# Res_Cut.net
KiCad netlist of a schematic drawn in EAGLE
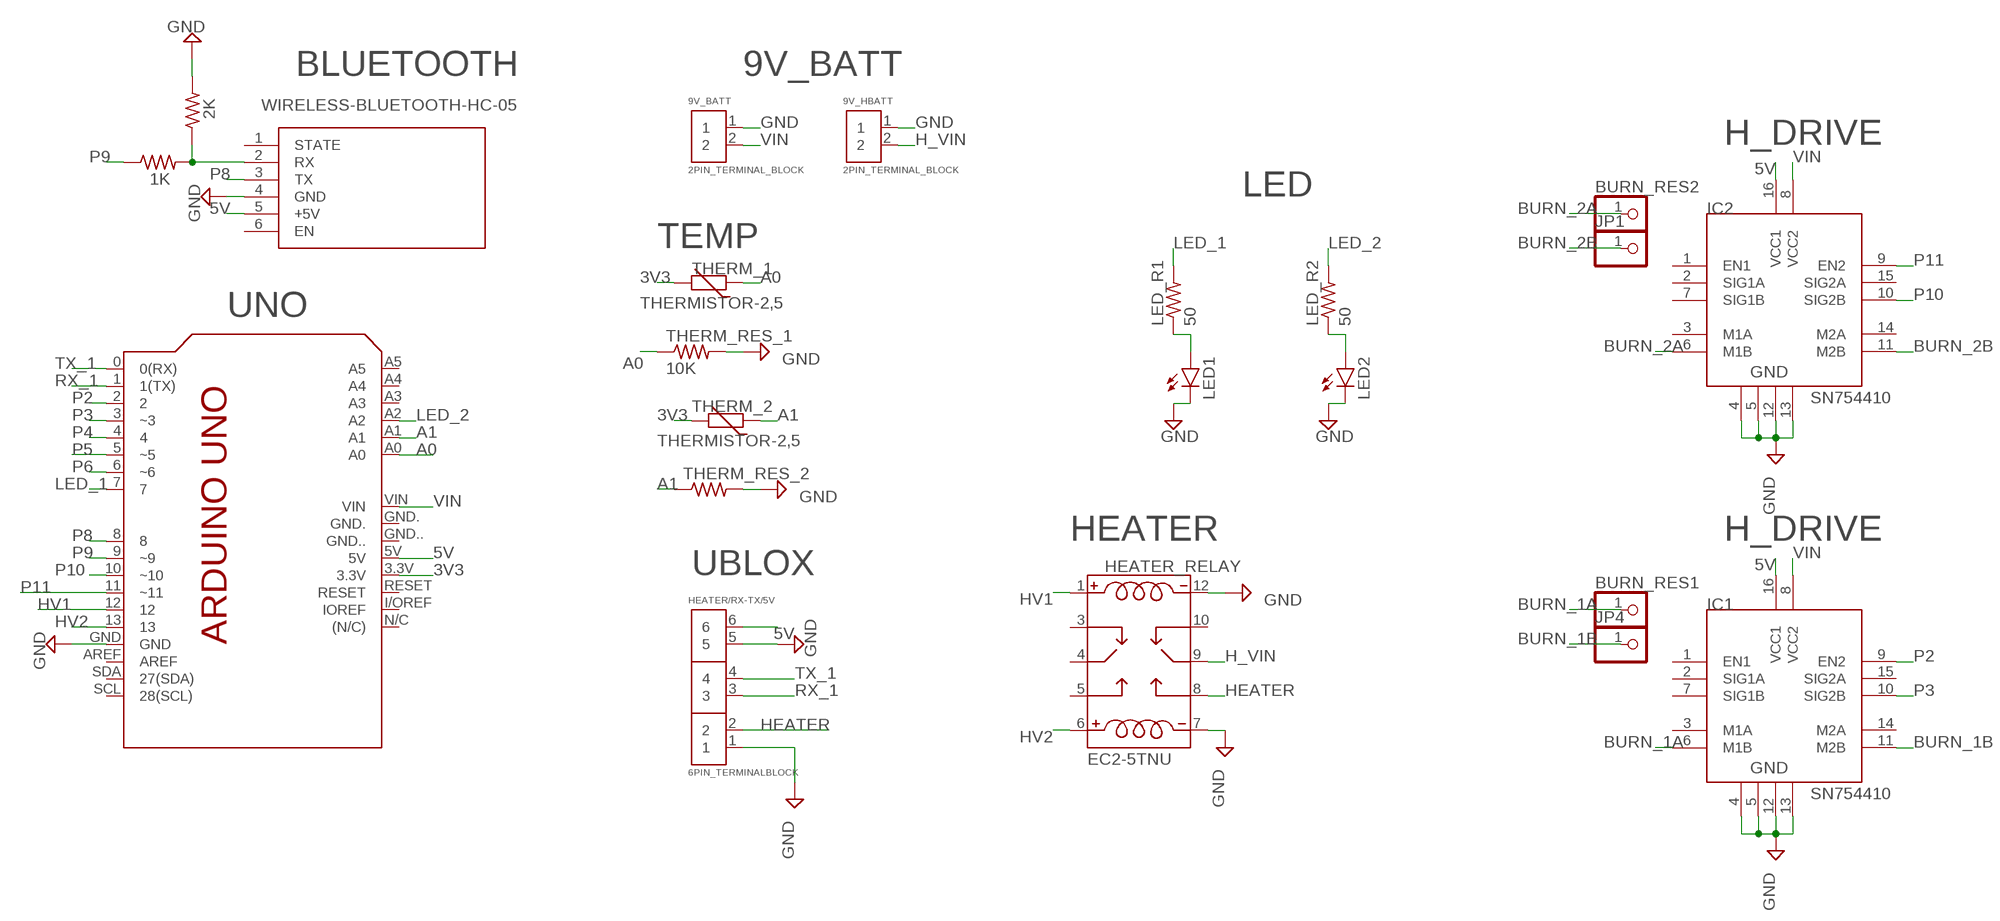
[diagram p0: schematic, sheet 1]

(export (version "E")
  (design (tool "Eeschema 10.0.6"))
  (components
    (comp (ref "9V_BATT")
      (value "2PIN_TERMINAL_BLOCK")
      (footprint "eagle-import:2PIN_TERMINAL_BLOCK")
      (fields
        (field (name "COMMENT") "282834-2")
        (field (name "DIGI-KEY_PART_NUMBER") "A98333-ND")
        (field (name "MF") "TE Connectivity")
      )
      (libsource (lib "eagle-import") (part "2PIN_TERMINAL_BLOCK"))
    )
    (comp (ref "9V_HBATT")
      (value "2PIN_TERMINAL_BLOCK")
      (footprint "eagle-import:2PIN_TERMINAL_BLOCK")
      (fields
        (field (name "COMMENT") "282834-2")
        (field (name "DIGI-KEY_PART_NUMBER") "A98333-ND")
        (field (name "MF") "TE Connectivity")
      )
      (libsource (lib "eagle-import") (part "2PIN_TERMINAL_BLOCK"))
    )
    (comp (ref "BLUE_R1")
      (value "1K")
      (footprint "eagle-import:0204_7")
      (libsource (lib "eagle-import") (part "R-US_0204/7"))
    )
    (comp (ref "BLUE_R2")
      (value "2K")
      (footprint "eagle-import:0204_7")
      (libsource (lib "eagle-import") (part "R-US_0204/7"))
    )
    (comp (ref "BURN_RES1")
      (value "PINHD-1X1CB")
      (footprint "eagle-import:1X01-CLEANBIG")
      (libsource (lib "eagle-import") (part "PINHD-1X1CB"))
    )
    (comp (ref "BURN_RES2")
      (value "PINHD-1X1CB")
      (footprint "eagle-import:1X01-CLEANBIG")
      (libsource (lib "eagle-import") (part "PINHD-1X1CB"))
    )
    (comp (ref "HEATER/RX-TX/5V")
      (value "6PIN_TERMINALBLOCK")
      (footprint "eagle-import:6PIN_TERMINALBLOCK")
      (libsource (lib "eagle-import") (part "6PIN_TERMINALBLOCK"))
    )
    (comp (ref "HEATER_RELAY")
      (value "EC2-5TNU")
      (footprint "eagle-import:RELAY_EC2-5TNU")
      (fields (field (name "MF") "KEMET"))
      (libsource (lib "eagle-import") (part "EC2-5TNU"))
    )
    (comp (ref "IC1")
      (value "SN754410")
      (footprint "eagle-import:DIP16")
      (libsource (lib "eagle-import") (part "SN754410"))
    )
    (comp (ref "IC2")
      (value "SN754410")
      (footprint "eagle-import:DIP16")
      (libsource (lib "eagle-import") (part "SN754410"))
    )
    (comp (ref "JP1")
      (value "PINHD-1X1CB")
      (footprint "eagle-import:1X01-CLEANBIG")
      (libsource (lib "eagle-import") (part "PINHD-1X1CB"))
    )
    (comp (ref "JP4")
      (value "PINHD-1X1CB")
      (footprint "eagle-import:1X01-CLEANBIG")
      (libsource (lib "eagle-import") (part "PINHD-1X1CB"))
    )
    (comp (ref "LED1")
      (value "TLLR4400")
      (footprint "eagle-import:LED3MM")
      (fields (field (name "MF") "VISHAY SEMICONDUCTOR"))
      (libsource (lib "eagle-import") (part "TLLR4400"))
    )
    (comp (ref "LED2")
      (value "TLLR4400")
      (footprint "eagle-import:LED3MM")
      (fields (field (name "MF") "VISHAY SEMICONDUCTOR"))
      (libsource (lib "eagle-import") (part "TLLR4400"))
    )
    (comp (ref "LED_R1")
      (value "50")
      (footprint "eagle-import:0204_7")
      (libsource (lib "eagle-import") (part "resistor_348_R-US_0204/7"))
    )
    (comp (ref "LED_R2")
      (value "50")
      (footprint "eagle-import:0204_7")
      (libsource (lib "eagle-import") (part "resistor_348_R-US_0204/7"))
    )
    (comp (ref "PCB1")
      (value "ARDUINO_UNO")
      (footprint "eagle-import:ARDUINO_UNO")
      (libsource (lib "eagle-import") (part "ARDUINO_UNO"))
    )
    (comp (ref "THERM_1")
      (value "THERMISTOR-2,5")
      (footprint "eagle-import:RS-2,5")
      (libsource (lib "eagle-import") (part "THERMISTOR-2,5"))
    )
    (comp (ref "THERM_2")
      (value "THERMISTOR-2,5")
      (footprint "eagle-import:RS-2,5")
      (libsource (lib "eagle-import") (part "THERMISTOR-2,5"))
    )
    (comp (ref "THERM_RES_1")
      (value "10K")
      (footprint "eagle-import:0204_7")
      (libsource (lib "eagle-import") (part "R-US_0204/7"))
    )
    (comp (ref "THERM_RES_2")
      (value "10K")
      (footprint "eagle-import:0204_7")
      (libsource (lib "eagle-import") (part "R-US_0204/7"))
    )
    (comp (ref "U$1")
      (value "WIRELESS-BLUETOOTH-HC-05")
      (footprint "eagle-import:WIRELESS-BLUETOOTH-HC-05")
      (libsource (lib "eagle-import") (part "WIRELESS-BLUETOOTH-HC-05"))
    )
  )
  (nets
    (net (code "1") (name "/3V3") (class "Default")
      (node (ref "PCB1") (pin "3.3V") (pinfunction "3.3V_3.3V") (pintype "bidirectional"))
      (node (ref "THERM_1") (pin "2") (pinfunction "2_2") (pintype "passive"))
      (node (ref "THERM_2") (pin "2") (pinfunction "2_2") (pintype "passive"))
    )
    (net (code "2") (name "/5V") (class "Default")
      (node (ref "HEATER/RX-TX/5V") (pin "6") (pinfunction "6_6") (pintype "passive"))
      (node (ref "IC1") (pin "16") (pinfunction "VCC1_16") (pintype "power_in"))
      (node (ref "IC2") (pin "16") (pinfunction "VCC1_16") (pintype "power_in"))
      (node (ref "PCB1") (pin "5V") (pinfunction "5V_5V") (pintype "bidirectional"))
      (node (ref "U$1") (pin "5") (pinfunction "+5V_5") (pintype "power_in"))
    )
    (net (code "3") (name "/A0") (class "Default")
      (node (ref "PCB1") (pin "A0") (pinfunction "A0_A0") (pintype "bidirectional"))
      (node (ref "THERM_1") (pin "1") (pinfunction "1_1") (pintype "passive"))
      (node (ref "THERM_RES_1") (pin "1") (pinfunction "1_1") (pintype "passive"))
    )
    (net (code "4") (name "/A1") (class "Default")
      (node (ref "PCB1") (pin "A1") (pinfunction "A1_A1") (pintype "bidirectional"))
      (node (ref "THERM_2") (pin "1") (pinfunction "1_1") (pintype "passive"))
      (node (ref "THERM_RES_2") (pin "1") (pinfunction "1_1") (pintype "passive"))
    )
    (net (code "5") (name "/BURN_1A") (class "Default")
      (node (ref "BURN_RES1") (pin "1") (pinfunction "1_1") (pintype "passive"))
      (node (ref "IC1") (pin "6") (pinfunction "M1B_6") (pintype "bidirectional"))
    )
    (net (code "6") (name "/BURN_1B") (class "Default")
      (node (ref "IC1") (pin "11") (pinfunction "M2B_11") (pintype "bidirectional"))
      (node (ref "JP4") (pin "1") (pinfunction "1_1") (pintype "passive"))
    )
    (net (code "7") (name "/BURN_2A") (class "Default")
      (node (ref "BURN_RES2") (pin "1") (pinfunction "1_1") (pintype "passive"))
      (node (ref "IC2") (pin "6") (pinfunction "M1B_6") (pintype "bidirectional"))
    )
    (net (code "8") (name "/BURN_2B") (class "Default")
      (node (ref "IC2") (pin "11") (pinfunction "M2B_11") (pintype "bidirectional"))
      (node (ref "JP1") (pin "1") (pinfunction "1_1") (pintype "passive"))
    )
    (net (code "9") (name "/HEATER") (class "Default")
      (node (ref "HEATER/RX-TX/5V") (pin "2") (pinfunction "2_2") (pintype "passive"))
      (node (ref "HEATER_RELAY") (pin "8") (pinfunction "NO_8") (pintype "passive"))
    )
    (net (code "10") (name "/HV1") (class "Default")
      (node (ref "HEATER_RELAY") (pin "1") (pinfunction "C1_1") (pintype "passive"))
      (node (ref "PCB1") (pin "12") (pinfunction "12_12") (pintype "bidirectional"))
    )
    (net (code "11") (name "/HV2") (class "Default")
      (node (ref "HEATER_RELAY") (pin "6") (pinfunction "C3_6") (pintype "passive"))
      (node (ref "PCB1") (pin "13") (pinfunction "13_13") (pintype "bidirectional"))
    )
    (net (code "12") (name "/H_VIN") (class "Default")
      (node (ref "9V_HBATT") (pin "2") (pinfunction "2_2") (pintype "passive"))
      (node (ref "HEATER_RELAY") (pin "9") (pinfunction "M_9") (pintype "passive"))
    )
    (net (code "13") (name "/LED_1") (class "Default")
      (node (ref "LED_R1") (pin "2") (pinfunction "2_2") (pintype "passive"))
      (node (ref "PCB1") (pin "7") (pinfunction "7_7") (pintype "bidirectional"))
    )
    (net (code "14") (name "/LED_2") (class "Default")
      (node (ref "LED_R2") (pin "2") (pinfunction "2_2") (pintype "passive"))
      (node (ref "PCB1") (pin "A2") (pinfunction "A2_A2") (pintype "bidirectional"))
    )
    (net (code "15") (name "/P2") (class "Default")
      (node (ref "IC1") (pin "9") (pinfunction "EN2_9") (pintype "bidirectional"))
      (node (ref "PCB1") (pin "2") (pinfunction "2_2") (pintype "bidirectional"))
    )
    (net (code "16") (name "/P3") (class "Default")
      (node (ref "IC1") (pin "10") (pinfunction "SIG2B_10") (pintype "bidirectional"))
      (node (ref "PCB1") (pin "3") (pinfunction "~{3}_3") (pintype "bidirectional"))
    )
    (net (code "17") (name "/P4") (class "Default")
      (node (ref "PCB1") (pin "4") (pinfunction "4_4") (pintype "bidirectional"))
    )
    (net (code "18") (name "/P5") (class "Default")
      (node (ref "PCB1") (pin "5") (pinfunction "~{5}_5") (pintype "bidirectional"))
    )
    (net (code "19") (name "/P6") (class "Default")
      (node (ref "PCB1") (pin "6") (pinfunction "~{6}_6") (pintype "bidirectional"))
    )
    (net (code "20") (name "/P8") (class "Default")
      (node (ref "PCB1") (pin "8") (pinfunction "8_8") (pintype "bidirectional"))
      (node (ref "U$1") (pin "3") (pinfunction "TX_3") (pintype "bidirectional"))
    )
    (net (code "21") (name "/P9") (class "Default")
      (node (ref "BLUE_R1") (pin "1") (pinfunction "1_1") (pintype "passive"))
      (node (ref "PCB1") (pin "9") (pinfunction "~{9}_9") (pintype "bidirectional"))
    )
    (net (code "22") (name "/P10") (class "Default")
      (node (ref "IC2") (pin "10") (pinfunction "SIG2B_10") (pintype "bidirectional"))
      (node (ref "PCB1") (pin "10") (pinfunction "~{10}_10") (pintype "bidirectional"))
    )
    (net (code "23") (name "/P11") (class "Default")
      (node (ref "IC2") (pin "9") (pinfunction "EN2_9") (pintype "bidirectional"))
      (node (ref "PCB1") (pin "11") (pinfunction "~{11}_11") (pintype "bidirectional"))
    )
    (net (code "24") (name "/RX_1") (class "Default")
      (node (ref "HEATER/RX-TX/5V") (pin "3") (pinfunction "3_3") (pintype "passive"))
      (node (ref "PCB1") (pin "1") (pinfunction "1(TX)_1") (pintype "bidirectional"))
    )
    (net (code "25") (name "/TX_1") (class "Default")
      (node (ref "HEATER/RX-TX/5V") (pin "4") (pinfunction "4_4") (pintype "passive"))
      (node (ref "PCB1") (pin "0") (pinfunction "0(RX)_0") (pintype "bidirectional"))
    )
    (net (code "26") (name "/VIN") (class "Default")
      (node (ref "9V_BATT") (pin "2") (pinfunction "2_2") (pintype "passive"))
      (node (ref "IC1") (pin "8") (pinfunction "VCC2_8") (pintype "power_in"))
      (node (ref "IC2") (pin "8") (pinfunction "VCC2_8") (pintype "power_in"))
      (node (ref "PCB1") (pin "VIN") (pinfunction "VIN_VIN") (pintype "bidirectional"))
    )
    (net (code "27") (name "GND") (class "Default")
      (node (ref "9V_BATT") (pin "1") (pinfunction "1_1") (pintype "passive"))
      (node (ref "9V_HBATT") (pin "1") (pinfunction "1_1") (pintype "passive"))
      (node (ref "BLUE_R2") (pin "2") (pinfunction "2_2") (pintype "passive"))
      (node (ref "HEATER/RX-TX/5V") (pin "1") (pinfunction "1_1") (pintype "passive"))
      (node (ref "HEATER/RX-TX/5V") (pin "5") (pinfunction "5_5") (pintype "passive"))
      (node (ref "HEATER_RELAY") (pin "12") (pinfunction "C2_12") (pintype "passive"))
      (node (ref "HEATER_RELAY") (pin "7") (pinfunction "C4_7") (pintype "passive"))
      (node (ref "IC1") (pin "12") (pinfunction "P12_12") (pintype "power_in"))
      (node (ref "IC1") (pin "13") (pinfunction "P13_13") (pintype "power_in"))
      (node (ref "IC1") (pin "4") (pinfunction "P4_4") (pintype "power_in"))
      (node (ref "IC1") (pin "5") (pinfunction "P5_5") (pintype "power_in"))
      (node (ref "IC2") (pin "12") (pinfunction "P12_12") (pintype "power_in"))
      (node (ref "IC2") (pin "13") (pinfunction "P13_13") (pintype "power_in"))
      (node (ref "IC2") (pin "4") (pinfunction "P4_4") (pintype "power_in"))
      (node (ref "IC2") (pin "5") (pinfunction "P5_5") (pintype "power_in"))
      (node (ref "LED1") (pin "K") (pinfunction "C_K") (pintype "passive"))
      (node (ref "LED2") (pin "K") (pinfunction "C_K") (pintype "passive"))
      (node (ref "PCB1") (pin "GND") (pinfunction "GND_GND") (pintype "bidirectional"))
      (node (ref "THERM_RES_1") (pin "2") (pinfunction "2_2") (pintype "passive"))
      (node (ref "THERM_RES_2") (pin "2") (pinfunction "2_2") (pintype "passive"))
      (node (ref "U$1") (pin "4") (pinfunction "GND_4") (pintype "power_in"))
    )
    (net (code "28") (name "Net-(LED1-PadA)") (class "Default")
      (node (ref "LED1") (pin "A") (pinfunction "A_A") (pintype "passive"))
      (node (ref "LED_R1") (pin "1") (pinfunction "1_1") (pintype "passive"))
    )
    (net (code "29") (name "Net-(LED2-PadA)") (class "Default")
      (node (ref "LED2") (pin "A") (pinfunction "A_A") (pintype "passive"))
      (node (ref "LED_R2") (pin "1") (pinfunction "1_1") (pintype "passive"))
    )
    (net (code "30") (name "Net-(U$1-RX)") (class "Default")
      (node (ref "BLUE_R1") (pin "2") (pinfunction "2_2") (pintype "passive"))
      (node (ref "BLUE_R2") (pin "1") (pinfunction "1_1") (pintype "passive"))
      (node (ref "U$1") (pin "2") (pinfunction "RX_2") (pintype "bidirectional"))
    )
    (net (code "31") (name "unconnected-(HEATER_RELAY-M1-Pad4)") (class "Default")
      (node (ref "HEATER_RELAY") (pin "4") (pinfunction "M1_4") (pintype "passive"))
    )
    (net (code "32") (name "unconnected-(HEATER_RELAY-NC-Pad10)") (class "Default")
      (node (ref "HEATER_RELAY") (pin "10") (pinfunction "NC_10") (pintype "passive"))
    )
    (net (code "33") (name "unconnected-(HEATER_RELAY-NC1-Pad3)") (class "Default")
      (node (ref "HEATER_RELAY") (pin "3") (pinfunction "NC1_3") (pintype "passive"))
    )
    (net (code "34") (name "unconnected-(HEATER_RELAY-NO1-Pad5)") (class "Default")
      (node (ref "HEATER_RELAY") (pin "5") (pinfunction "NO1_5") (pintype "passive"))
    )
    (net (code "35") (name "unconnected-(IC1-EN1-Pad1)") (class "Default")
      (node (ref "IC1") (pin "1") (pinfunction "EN1_1") (pintype "bidirectional"))
    )
    (net (code "36") (name "unconnected-(IC1-M1A-Pad3)") (class "Default")
      (node (ref "IC1") (pin "3") (pinfunction "M1A_3") (pintype "bidirectional"))
    )
    (net (code "37") (name "unconnected-(IC1-M2A-Pad14)") (class "Default")
      (node (ref "IC1") (pin "14") (pinfunction "M2A_14") (pintype "bidirectional"))
    )
    (net (code "38") (name "unconnected-(IC1-SIG1A-Pad2)") (class "Default")
      (node (ref "IC1") (pin "2") (pinfunction "SIG1A_2") (pintype "bidirectional"))
    )
    (net (code "39") (name "unconnected-(IC1-SIG1B-Pad7)") (class "Default")
      (node (ref "IC1") (pin "7") (pinfunction "SIG1B_7") (pintype "bidirectional"))
    )
    (net (code "40") (name "unconnected-(IC1-SIG2A-Pad15)") (class "Default")
      (node (ref "IC1") (pin "15") (pinfunction "SIG2A_15") (pintype "bidirectional"))
    )
    (net (code "41") (name "unconnected-(IC2-EN1-Pad1)") (class "Default")
      (node (ref "IC2") (pin "1") (pinfunction "EN1_1") (pintype "bidirectional"))
    )
    (net (code "42") (name "unconnected-(IC2-M1A-Pad3)") (class "Default")
      (node (ref "IC2") (pin "3") (pinfunction "M1A_3") (pintype "bidirectional"))
    )
    (net (code "43") (name "unconnected-(IC2-M2A-Pad14)") (class "Default")
      (node (ref "IC2") (pin "14") (pinfunction "M2A_14") (pintype "bidirectional"))
    )
    (net (code "44") (name "unconnected-(IC2-SIG1A-Pad2)") (class "Default")
      (node (ref "IC2") (pin "2") (pinfunction "SIG1A_2") (pintype "bidirectional"))
    )
    (net (code "45") (name "unconnected-(IC2-SIG1B-Pad7)") (class "Default")
      (node (ref "IC2") (pin "7") (pinfunction "SIG1B_7") (pintype "bidirectional"))
    )
    (net (code "46") (name "unconnected-(IC2-SIG2A-Pad15)") (class "Default")
      (node (ref "IC2") (pin "15") (pinfunction "SIG2A_15") (pintype "bidirectional"))
    )
    (net (code "47") (name "unconnected-(PCB1-(N{slash}C)-PadN{slash}C)") (class "Default")
      (node (ref "PCB1") (pin "N/C") (pinfunction "(N/C)_N/C") (pintype "bidirectional"))
    )
    (net (code "48") (name "unconnected-(PCB1-27(SDA)-PadSDA)") (class "Default")
      (node (ref "PCB1") (pin "SDA") (pinfunction "27(SDA)_SDA") (pintype "bidirectional"))
    )
    (net (code "49") (name "unconnected-(PCB1-28(SCL)-PadSCL)") (class "Default")
      (node (ref "PCB1") (pin "SCL") (pinfunction "28(SCL)_SCL") (pintype "bidirectional"))
    )
    (net (code "50") (name "unconnected-(PCB1-IOREF-PadI{slash}OREF)") (class "Default")
      (node (ref "PCB1") (pin "I/OREF") (pinfunction "IOREF_I/OREF") (pintype "bidirectional"))
    )
    (net (code "51") (name "unconnected-(PCB1-PadA3)") (class "Default")
      (node (ref "PCB1") (pin "A3") (pinfunction "A3_A3") (pintype "bidirectional"))
    )
    (net (code "52") (name "unconnected-(PCB1-PadA4)") (class "Default")
      (node (ref "PCB1") (pin "A4") (pinfunction "A4_A4") (pintype "bidirectional"))
    )
    (net (code "53") (name "unconnected-(PCB1-PadA5)") (class "Default")
      (node (ref "PCB1") (pin "A5") (pinfunction "A5_A5") (pintype "bidirectional"))
    )
    (net (code "54") (name "unconnected-(PCB1-PadAREF)") (class "Default")
      (node (ref "PCB1") (pin "AREF") (pinfunction "AREF_AREF") (pintype "bidirectional"))
    )
    (net (code "55") (name "unconnected-(PCB1-PadGND.)") (class "Default")
      (node (ref "PCB1") (pin "GND.") (pinfunction "GND._GND.") (pintype "bidirectional"))
    )
    (net (code "56") (name "unconnected-(PCB1-PadGND..)") (class "Default")
      (node (ref "PCB1") (pin "GND..") (pinfunction "GND.._GND..") (pintype "bidirectional"))
    )
    (net (code "57") (name "unconnected-(PCB1-PadRESET)") (class "Default")
      (node (ref "PCB1") (pin "RESET") (pinfunction "RESET_RESET") (pintype "bidirectional"))
    )
    (net (code "58") (name "unconnected-(U$1-EN-Pad6)") (class "Default")
      (node (ref "U$1") (pin "6") (pinfunction "EN_6") (pintype "bidirectional"))
    )
    (net (code "59") (name "unconnected-(U$1-STATE-Pad1)") (class "Default")
      (node (ref "U$1") (pin "1") (pinfunction "STATE_1") (pintype "bidirectional"))
    )
  )
)
